# solar_power.net
KiCad netlist of a schematic drawn in Altium Designer
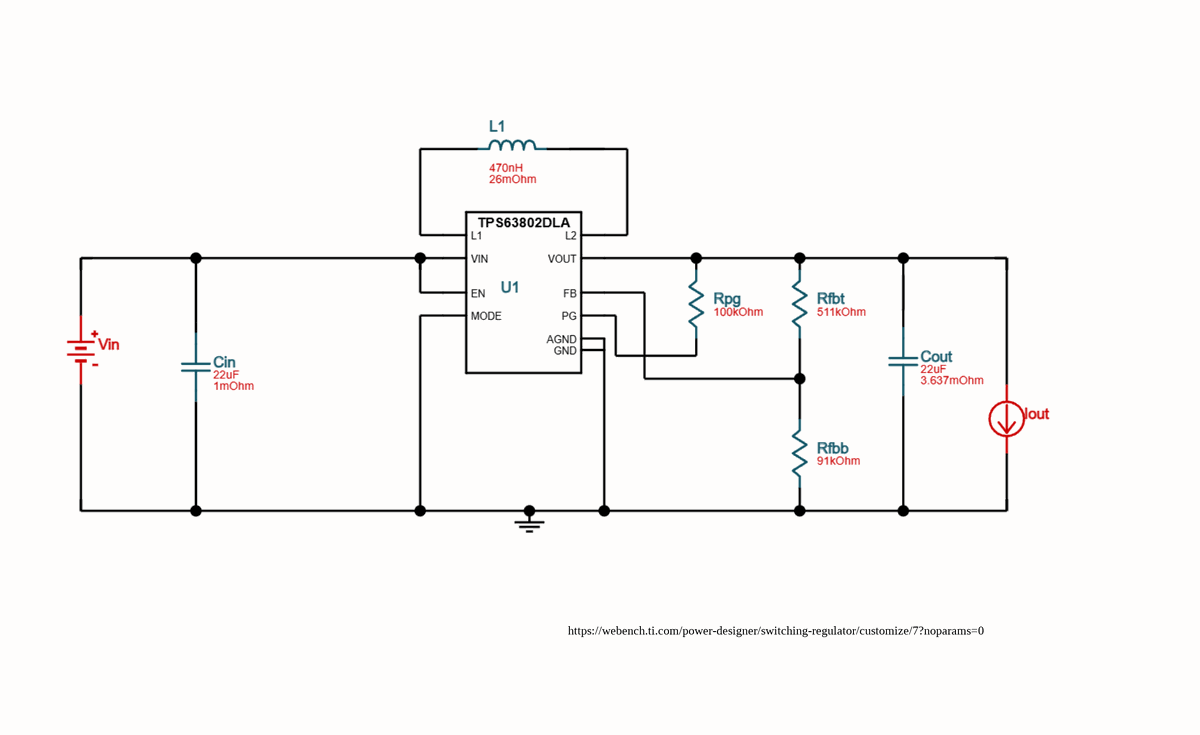
[diagram p0: solar_power.SchDoc, left]
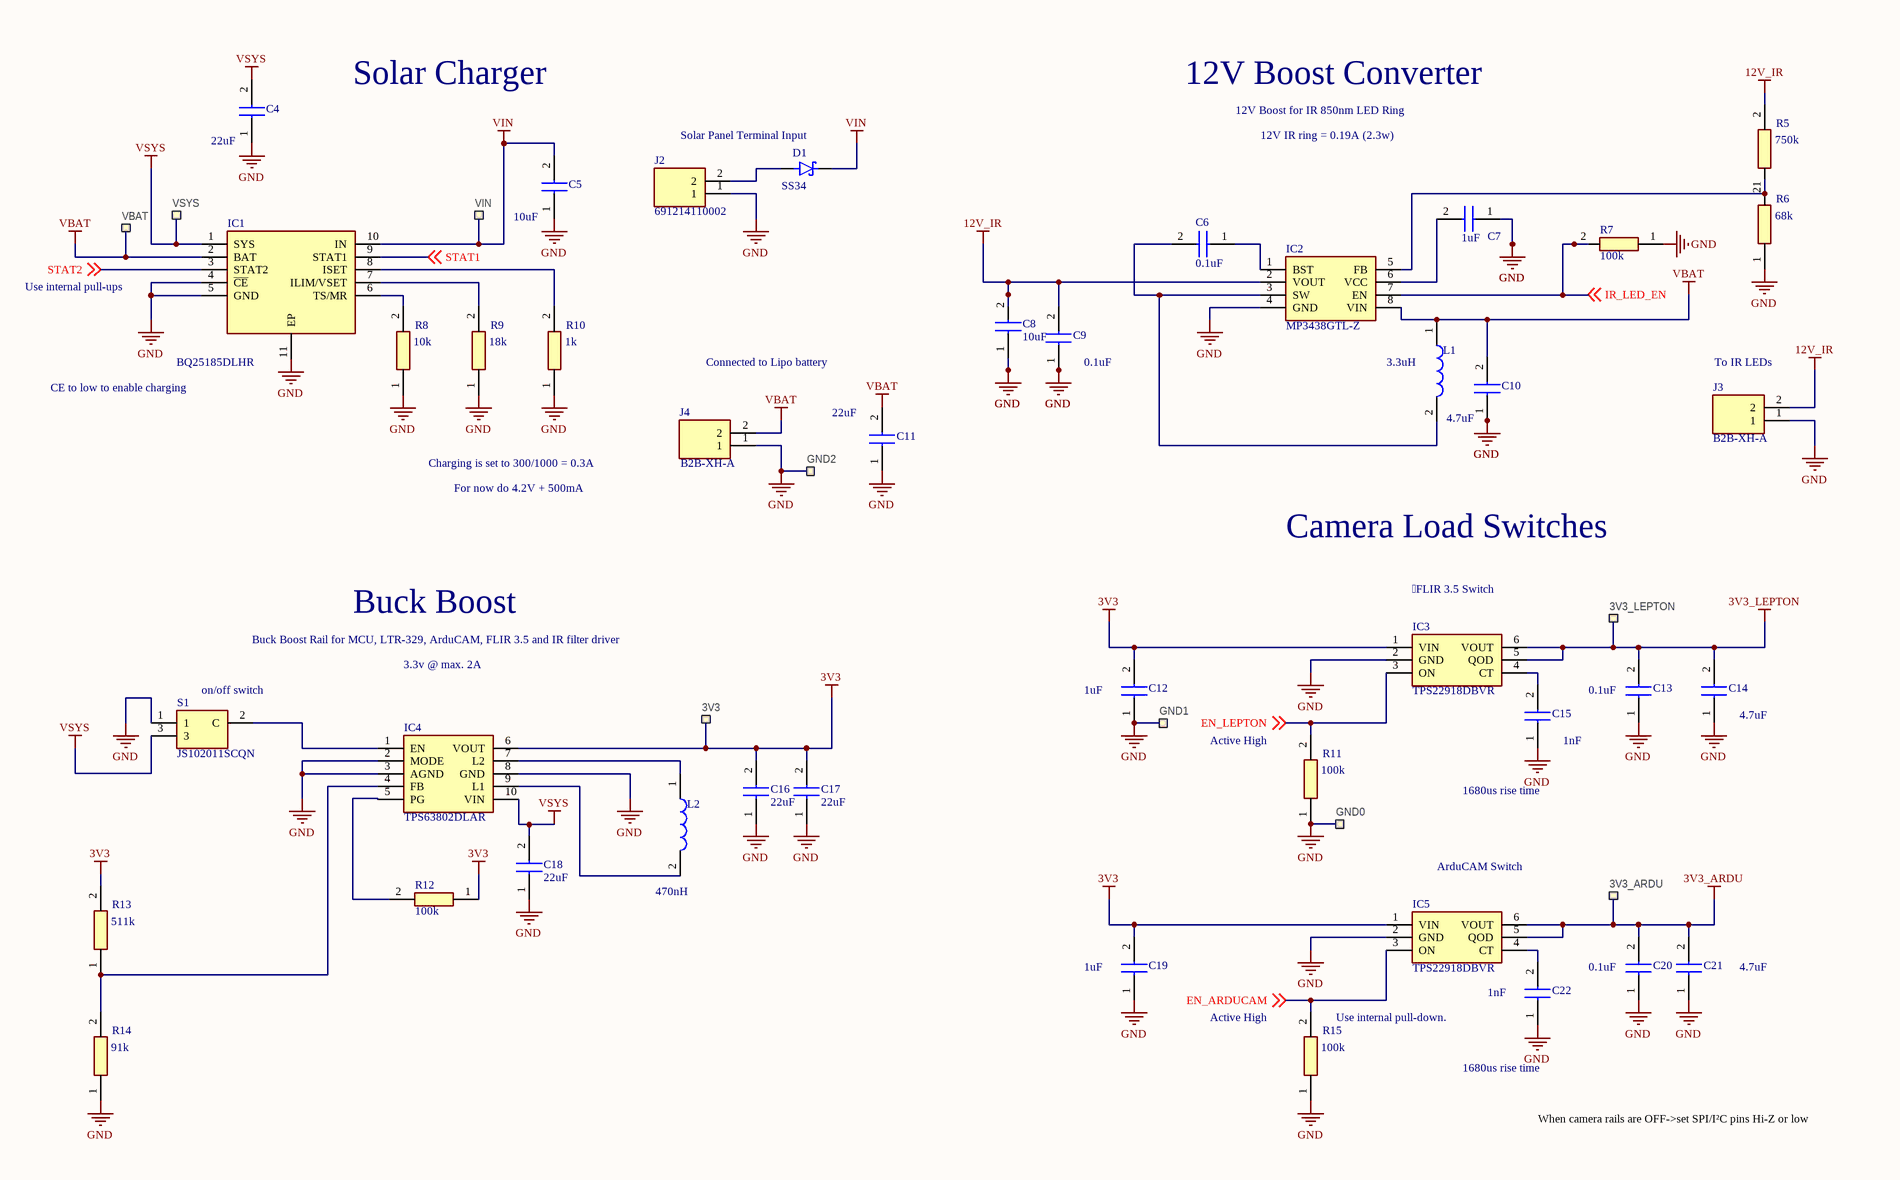
[diagram p1: solar_power.SchDoc, right]

(export (version "E")
  (design (tool "Eeschema 10.0.6"))
  (components
    (comp (ref "3V3")
      (value "Ø1.0mm,SMD")
      (footprint "TP_SMD_D1.0mm")
      (description "1.0mm circular SMD testpad")
      (fields
        (field (name "PART NUMBER") "TP_SMD_Ø1.0MM")
        (field (name "MANUFACTURER") "Nordic Semiconductor")
        (field (name "AUTHOR") "rsk")
      )
      (libsource (lib "AltiumLib") (part "TESTPAD"))
    )
    (comp (ref "3V3_ARDU")
      (value "Ø1.0mm,SMD")
      (footprint "TP_SMD_D1.0mm")
      (description "1.0mm circular SMD testpad")
      (fields
        (field (name "PART NUMBER") "TP_SMD_Ø1.0MM")
        (field (name "MANUFACTURER") "Nordic Semiconductor")
        (field (name "AUTHOR") "rsk")
      )
      (libsource (lib "AltiumLib") (part "TESTPAD"))
    )
    (comp (ref "3V3_LEPTON")
      (value "Ø1.0mm,SMD")
      (footprint "TP_SMD_D1.0mm")
      (description "1.0mm circular SMD testpad")
      (fields
        (field (name "PART NUMBER") "TP_SMD_Ø1.0MM")
        (field (name "MANUFACTURER") "Nordic Semiconductor")
        (field (name "AUTHOR") "rsk")
      )
      (libsource (lib "AltiumLib") (part "TESTPAD"))
    )
    (comp (ref "C4")
      (value "22uF")
      (footprint "SamacSys:CAPC2114X95N")
      (description "MSASL219LB5226MTNA01 0805 CAP 25V")
      (fields (field (name "MANUFACTURER_PART_NUMBER") "MSASL219LB5226MTNA01"))
      (libsource (lib "*") (part "MSASL219LB5226MTNA01"))
    )
    (comp (ref "C5")
      (value "10uF")
      (footprint "SamacSys:CAPC2114X95N")
      (description "MSASL219LB5226MTNA01 0805 CAP 25V")
      (fields (field (name "MANUFACTURER_PART_NUMBER") "MSASL219LB5226MTNA01"))
      (libsource (lib "*") (part "MSASL219LB5226MTNA01"))
    )
    (comp (ref "C6")
      (value "0.1uF")
      (footprint "SamacSys:CAPC1608X90N")
      (description "0603 CAP X5R 25V")
      (fields
        (field (name "MANUFACTURER_PART_NUMBER") "CC0603KRX7R0BB104")
        (field (name "MOUSER PART NUMBER") "603-CC603KRX7R0BB104")
      )
      (libsource (lib "*") (part "CC0603KRX7R0BB104"))
    )
    (comp (ref "C7")
      (value "1uF")
      (footprint "SamacSys:CAPC1608X90N")
      (description "0603 CAP X5R 25V")
      (fields
        (field (name "MANUFACTURER_PART_NUMBER") "CC0603KRX7R0BB104")
        (field (name "MOUSER PART NUMBER") "603-CC603KRX7R0BB104")
      )
      (libsource (lib "*") (part "CC0603KRX7R0BB104"))
    )
    (comp (ref "C8")
      (value "10uF")
      (footprint "SamacSys:CAPC2114X95N")
      (description "MSASL219LB5226MTNA01 0805 CAP 25V")
      (fields (field (name "MANUFACTURER_PART_NUMBER") "MSASL219LB5226MTNA01"))
      (libsource (lib "*") (part "MSASL219LB5226MTNA01"))
    )
    (comp (ref "C9")
      (value "0.1uF")
      (footprint "SamacSys:CAPC1608X90N")
      (description "0603 CAP X5R 25V")
      (fields
        (field (name "MANUFACTURER_PART_NUMBER") "CC0603KRX7R0BB104")
        (field (name "MOUSER PART NUMBER") "603-CC603KRX7R0BB104")
      )
      (libsource (lib "*") (part "CC0603KRX7R0BB104"))
    )
    (comp (ref "C10")
      (value "4.7uF")
      (footprint "SamacSys:CAPC2114X95N")
      (description "MSASL219LB5226MTNA01 0805 CAP 25V")
      (fields (field (name "MANUFACTURER_PART_NUMBER") "MSASL219LB5226MTNA01"))
      (libsource (lib "*") (part "MSASL219LB5226MTNA01"))
    )
    (comp (ref "C11")
      (value "22uF")
      (footprint "SamacSys:CAPC2114X95N")
      (description "MSASL219LB5226MTNA01 0805 CAP 25V")
      (fields (field (name "MANUFACTURER_PART_NUMBER") "MSASL219LB5226MTNA01"))
      (libsource (lib "*") (part "MSASL219LB5226MTNA01"))
    )
    (comp (ref "C12")
      (value "1uF")
      (footprint "SamacSys:CAPC1608X90N")
      (description "0603 CAP X5R 25V")
      (fields
        (field (name "MANUFACTURER_PART_NUMBER") "CC0603KRX7R0BB104")
        (field (name "MOUSER PART NUMBER") "603-CC603KRX7R0BB104")
      )
      (libsource (lib "*") (part "CC0603KRX7R0BB104"))
    )
    (comp (ref "C13")
      (value "0.1uF")
      (footprint "SamacSys:CAPC1608X90N")
      (description "0603 CAP X5R 25V")
      (fields
        (field (name "MANUFACTURER_PART_NUMBER") "CC0603KRX7R0BB104")
        (field (name "MOUSER PART NUMBER") "603-CC603KRX7R0BB104")
      )
      (libsource (lib "*") (part "CC0603KRX7R0BB104"))
    )
    (comp (ref "C14")
      (value "4.7uF")
      (footprint "SamacSys:CAPC1608X90N")
      (description "0603 CAP X5R 25V")
      (fields
        (field (name "MANUFACTURER_PART_NUMBER") "CC0603KRX7R0BB104")
        (field (name "MOUSER PART NUMBER") "603-CC603KRX7R0BB104")
      )
      (libsource (lib "*") (part "CC0603KRX7R0BB104"))
    )
    (comp (ref "C15")
      (value "1nF")
      (footprint "SamacSys:CAPC1608X90N")
      (description "0603 CAP X5R 50V")
      (fields
        (field (name "MANUFACTURER_PART_NUMBER") "CC0603KRX7R0BB104")
        (field (name "MOUSER PART NUMBER") "603-CC603KRX7R0BB104")
      )
      (libsource (lib "*") (part "CC0603KRX7R0BB104"))
    )
    (comp (ref "C16")
      (value "22uF")
      (footprint "SamacSys:CAPC2114X95N")
      (description "MSASL219LB5226MTNA01 0805 CAP 25V")
      (fields (field (name "MANUFACTURER_PART_NUMBER") "MSASL219LB5226MTNA01"))
      (libsource (lib "*") (part "MSASL219LB5226MTNA01"))
    )
    (comp (ref "C17")
      (value "22uF")
      (footprint "SamacSys:CAPC2114X95N")
      (description "MSASL219LB5226MTNA01 0805 CAP 25V")
      (fields (field (name "MANUFACTURER_PART_NUMBER") "MSASL219LB5226MTNA01"))
      (libsource (lib "*") (part "MSASL219LB5226MTNA01"))
    )
    (comp (ref "C18")
      (value "22uF")
      (footprint "SamacSys:CAPC2114X95N")
      (description "MSASL219LB5226MTNA01 0805 CAP 25V")
      (fields (field (name "MANUFACTURER_PART_NUMBER") "MSASL219LB5226MTNA01"))
      (libsource (lib "*") (part "MSASL219LB5226MTNA01"))
    )
    (comp (ref "C19")
      (value "1uF")
      (footprint "SamacSys:CAPC1608X90N")
      (description "0603 CAP X5R 25V")
      (fields
        (field (name "MANUFACTURER_PART_NUMBER") "CC0603KRX7R0BB104")
        (field (name "MOUSER PART NUMBER") "603-CC603KRX7R0BB104")
      )
      (libsource (lib "*") (part "CC0603KRX7R0BB104"))
    )
    (comp (ref "C20")
      (value "0.1uF")
      (footprint "SamacSys:CAPC1608X90N")
      (description "0603 CAP X5R 25V")
      (fields
        (field (name "MANUFACTURER_PART_NUMBER") "CC0603KRX7R0BB104")
        (field (name "MOUSER PART NUMBER") "603-CC603KRX7R0BB104")
      )
      (libsource (lib "*") (part "CC0603KRX7R0BB104"))
    )
    (comp (ref "C21")
      (value "4.7uF")
      (footprint "SamacSys:CAPC1608X90N")
      (description "0603 CAP X5R 25V")
      (fields
        (field (name "MANUFACTURER_PART_NUMBER") "CC0603KRX7R0BB104")
        (field (name "MOUSER PART NUMBER") "603-CC603KRX7R0BB104")
      )
      (libsource (lib "*") (part "CC0603KRX7R0BB104"))
    )
    (comp (ref "C22")
      (value "1nF")
      (footprint "SamacSys:CAPC1608X90N")
      (description "0603 CAP X5R 50V")
      (fields
        (field (name "MANUFACTURER_PART_NUMBER") "CC0603KRX7R0BB104")
        (field (name "MOUSER PART NUMBER") "603-CC603KRX7R0BB104")
      )
      (libsource (lib "*") (part "CC0603KRX7R0BB104"))
    )
    (comp (ref "D1")
      (value "SS34")
      (footprint "DIOM7959X265N")
      (description "Diode Schottky 40 V 3A Surface Mount SMC (DO-214AB)")
      (fields (field (name "MF") "onsemi"))
      (libsource (lib "SamacSys") (part "SS34"))
    )
    (comp (ref "GND0")
      (value "Ø1.0mm,SMD")
      (footprint "TP_SMD_D1.0mm")
      (description "1.0mm circular SMD testpad")
      (fields
        (field (name "PART NUMBER") "TP_SMD_Ø1.0MM")
        (field (name "MANUFACTURER") "Nordic Semiconductor")
        (field (name "AUTHOR") "rsk")
      )
      (libsource (lib "") (part "TESTPAD_1"))
    )
    (comp (ref "GND1")
      (value "Ø1.0mm,SMD")
      (footprint "TP_SMD_D1.0mm")
      (description "1.0mm circular SMD testpad")
      (fields
        (field (name "PART NUMBER") "TP_SMD_Ø1.0MM")
        (field (name "MANUFACTURER") "Nordic Semiconductor")
        (field (name "AUTHOR") "rsk")
      )
      (libsource (lib "") (part "TESTPAD_1"))
    )
    (comp (ref "GND2")
      (value "Ø1.0mm,SMD")
      (footprint "TP_SMD_D1.0mm")
      (description "1.0mm circular SMD testpad")
      (fields
        (field (name "PART NUMBER") "TP_SMD_Ø1.0MM")
        (field (name "MANUFACTURER") "Nordic Semiconductor")
        (field (name "AUTHOR") "rsk")
      )
      (libsource (lib "") (part "TESTPAD_1"))
    )
    (comp (ref "IC1")
      (value "BQ25185DLHR")
      (footprint "SamacSys:SON40P220X200X80-11N")
      (description "Integrated Circuit")
      (fields (field (name "MOUSER PART NUMBER") "595-BQ25185DLHR"))
      (libsource (lib "*") (part "BQ25185DLHR"))
    )
    (comp (ref "IC2")
      (value "MP3438GTL-Z")
      (footprint "SamacSys:SOTFL50P160X60-8N")
      (description "Integrated Circuit")
      (fields (field (name "MOUSER PART NUMBER") "946-MP3438GTL-Z"))
      (libsource (lib "*") (part "MP3438GTL-Z"))
    )
    (comp (ref "IC3")
      (value "TPS22918DBVR")
      (footprint "SamacSys:SOT95P280X145-6N")
      (description "Integrated Circuit")
      (fields (field (name "MOUSER PART NUMBER") "595-TPS22918DBVR"))
      (libsource (lib "*") (part "TPS22918DBVR"))
    )
    (comp (ref "IC4")
      (value "TPS63802DLAR")
      (footprint "SamacSys:TPS63802DLAR")
      (description "Integrated Circuit")
      (fields (field (name "MOUSER PART NUMBER") "595-TPS63802DLAR"))
      (libsource (lib "*") (part "TPS63802DLAR"))
    )
    (comp (ref "IC5")
      (value "TPS22918DBVR")
      (footprint "SamacSys:SOT95P280X145-6N")
      (description "Integrated Circuit")
      (fields (field (name "MOUSER PART NUMBER") "595-TPS22918DBVR"))
      (libsource (lib "*") (part "TPS22918DBVR"))
    )
    (comp (ref "J2")
      (value "691214110002")
      (footprint "SamacSys:691214110002")
      (description "Connector")
      (fields (field (name "MOUSER PART NUMBER") "710-691214110002"))
      (libsource (lib "*") (part "691214110002"))
    )
    (comp (ref "J3")
      (value "B2B-XH-A")
      (footprint "SamacSys:SHDR2W64P0X250_1X2_740X575X700P")
      (description "Connector")
      (libsource (lib "*") (part "B2B-XH-A"))
    )
    (comp (ref "J4")
      (value "B2B-XH-A")
      (footprint "SamacSys:SHDR2W64P0X250_1X2_740X575X700P")
      (description "Connector")
      (libsource (lib "*") (part "B2B-XH-A"))
    )
    (comp (ref "L1")
      (value "3.3uH")
      (footprint "SamacSys:MPLAL40203R3")
      (description "MPL-AL4020-3R3")
      (fields (field (name "MOUSER PART NUMBER") "946-MPL-AL4020-3R3"))
      (libsource (lib "*") (part "MPL-AL4020-3R3"))
    )
    (comp (ref "L2")
      (value "470nH")
      (footprint "SamacSys:1285ASH1R0MP2")
      (description "DFE201610E-R47M=P2")
      (fields (field (name "MOUSER PART NUMBER") "81-DFE201610E-R47MP2"))
      (libsource (lib "*") (part "DFE201610E-R47M=P2"))
    )
    (comp (ref "R5")
      (value "750k")
      (footprint "SamacSys:RESC1608X55N")
      (description "Resistor SMD 0603 1% 0.25W")
      (fields (field (name "MANUFACTURER_PART_NUMBER") "RC0603FR0710KL"))
      (libsource (lib "") (part "RC0603FR0710KL_1"))
    )
    (comp (ref "R6")
      (value "68k")
      (footprint "SamacSys:RESC1608X55N")
      (description "Resistor SMD 0603 1% 0.25W")
      (fields (field (name "MANUFACTURER_PART_NUMBER") "RC0603FR0710KL"))
      (libsource (lib "") (part "RC0603FR0710KL_1"))
    )
    (comp (ref "R7")
      (value "100k")
      (footprint "SamacSys:RESC1608X55N")
      (description "Resistor SMD 0603 1% 0.1W")
      (fields (field (name "MANUFACTURER_PART_NUMBER") "RC0603FR0710KL"))
      (libsource (lib "*") (part "RC0603FR0710KL"))
    )
    (comp (ref "R8")
      (value "10k")
      (footprint "SamacSys:RESC1608X55N")
      (description "Resistor SMD 0603 1% 1/10")
      (fields (field (name "MANUFACTURER_PART_NUMBER") "RC0603FR0710KL"))
      (libsource (lib "") (part "RC0603FR0710KL_1"))
    )
    (comp (ref "R9")
      (value "18k")
      (footprint "SamacSys:RESC1608X55N")
      (description "Resistor SMD 0603 1% 1/10")
      (fields (field (name "MANUFACTURER_PART_NUMBER") "RC0603FR0710KL"))
      (libsource (lib "") (part "RC0603FR0710KL_1"))
    )
    (comp (ref "R10")
      (value "1k")
      (footprint "SamacSys:RESC1608X55N")
      (description "Resistor SMD 0603 1% 1/10")
      (fields (field (name "MANUFACTURER_PART_NUMBER") "RC0603FR0710KL"))
      (libsource (lib "") (part "RC0603FR0710KL_1"))
    )
    (comp (ref "R11")
      (value "100k")
      (footprint "SamacSys:RESC1608X55N")
      (description "Resistor SMD 0603 1% 0.1W")
      (fields (field (name "MANUFACTURER_PART_NUMBER") "RC0603FR0710KL"))
      (libsource (lib "") (part "RC0603FR0710KL_1"))
    )
    (comp (ref "R12")
      (value "100k")
      (footprint "SamacSys:RESC1608X55N")
      (description "Resistor SMD 0603 1% 0.1W")
      (fields (field (name "MANUFACTURER_PART_NUMBER") "RC0603FR0710KL"))
      (libsource (lib "*") (part "RC0603FR0710KL"))
    )
    (comp (ref "R13")
      (value "511k")
      (footprint "SamacSys:RESC1608X55N")
      (description "Resistor SMD 0603 1% 1/10")
      (fields (field (name "MANUFACTURER_PART_NUMBER") "RC0603FR0710KL"))
      (libsource (lib "") (part "RC0603FR0710KL_1"))
    )
    (comp (ref "R14")
      (value "91k")
      (footprint "SamacSys:RESC1608X55N")
      (description "Resistor SMD 0603 1% 1/10")
      (fields (field (name "MANUFACTURER_PART_NUMBER") "RC0603FR0710KL"))
      (libsource (lib "") (part "RC0603FR0710KL_1"))
    )
    (comp (ref "R15")
      (value "100k")
      (footprint "SamacSys:RESC1608X55N")
      (description "Resistor SMD 0603 1% 0.1W")
      (fields (field (name "MANUFACTURER_PART_NUMBER") "RC0603FR0710KL"))
      (libsource (lib "") (part "RC0603FR0710KL_1"))
    )
    (comp (ref "S1")
      (value "JS102011SCQN")
      (footprint "SamacSys:JS102011SCQN")
      (description "Switch")
      (fields (field (name "MOUSER PART NUMBER") "611-JS102011SCQN"))
      (libsource (lib "*") (part "JS102011SCQN"))
    )
    (comp (ref "VBAT")
      (value "Ø1.0mm,SMD")
      (footprint "TP_SMD_D1.0mm")
      (description "1.0mm circular SMD testpad")
      (fields
        (field (name "PART NUMBER") "TP_SMD_Ø1.0MM")
        (field (name "MANUFACTURER") "Nordic Semiconductor")
        (field (name "AUTHOR") "rsk")
      )
      (libsource (lib "AltiumLib") (part "TESTPAD"))
    )
    (comp (ref "VIN")
      (value "Ø1.0mm,SMD")
      (footprint "TP_SMD_D1.0mm")
      (description "1.0mm circular SMD testpad")
      (fields
        (field (name "PART NUMBER") "TP_SMD_Ø1.0MM")
        (field (name "MANUFACTURER") "Nordic Semiconductor")
        (field (name "AUTHOR") "rsk")
      )
      (libsource (lib "AltiumLib") (part "TESTPAD"))
    )
    (comp (ref "VSYS")
      (value "Ø1.0mm,SMD")
      (footprint "TP_SMD_D1.0mm")
      (description "1.0mm circular SMD testpad")
      (fields
        (field (name "PART NUMBER") "TP_SMD_Ø1.0MM")
        (field (name "MANUFACTURER") "Nordic Semiconductor")
        (field (name "AUTHOR") "rsk")
      )
      (libsource (lib "AltiumLib") (part "TESTPAD"))
    )
  )
  (nets
    (net (code "1") (name "3V3") (class "Default")
      (node (ref "3V3") (pin "1") (pinfunction "1_1") (pintype "passive"))
      (node (ref "C12") (pin "2") (pinfunction "2_2") (pintype "passive"))
      (node (ref "C16") (pin "2") (pinfunction "2_2") (pintype "passive"))
      (node (ref "C17") (pin "2") (pinfunction "2_2") (pintype "passive"))
      (node (ref "C19") (pin "2") (pinfunction "2_2") (pintype "passive"))
      (node (ref "IC3") (pin "1") (pinfunction "VIN_1") (pintype "passive"))
      (node (ref "IC4") (pin "6") (pinfunction "VOUT_6") (pintype "passive"))
      (node (ref "IC5") (pin "1") (pinfunction "VIN_1") (pintype "passive"))
      (node (ref "R12") (pin "1") (pinfunction "1_1") (pintype "passive"))
      (node (ref "R13") (pin "2") (pinfunction "2_2") (pintype "passive"))
    )
    (net (code "2") (name "3V3_ARDU") (class "Default")
      (node (ref "3V3_ARDU") (pin "1") (pinfunction "1_1") (pintype "passive"))
      (node (ref "C20") (pin "2") (pinfunction "2_2") (pintype "passive"))
      (node (ref "C21") (pin "2") (pinfunction "2_2") (pintype "passive"))
      (node (ref "IC5") (pin "5") (pinfunction "QOD_5") (pintype "passive"))
      (node (ref "IC5") (pin "6") (pinfunction "VOUT_6") (pintype "passive"))
    )
    (net (code "3") (name "3V3_LEPTON") (class "Default")
      (node (ref "3V3_LEPTON") (pin "1") (pinfunction "1_1") (pintype "passive"))
      (node (ref "C13") (pin "2") (pinfunction "2_2") (pintype "passive"))
      (node (ref "C14") (pin "2") (pinfunction "2_2") (pintype "passive"))
      (node (ref "IC3") (pin "5") (pinfunction "QOD_5") (pintype "passive"))
      (node (ref "IC3") (pin "6") (pinfunction "VOUT_6") (pintype "passive"))
    )
    (net (code "4") (name "12V_IR") (class "Default")
      (node (ref "C8") (pin "2") (pinfunction "2_2") (pintype "passive"))
      (node (ref "C9") (pin "2") (pinfunction "2_2") (pintype "passive"))
      (node (ref "IC2") (pin "2") (pinfunction "VOUT_2") (pintype "passive"))
      (node (ref "J3") (pin "2") (pinfunction "2_2") (pintype "passive"))
      (node (ref "R5") (pin "2") (pinfunction "2_2") (pintype "passive"))
    )
    (net (code "5") (name "EN_ARDUCAM") (class "Default")
      (node (ref "IC5") (pin "3") (pinfunction "ON_3") (pintype "passive"))
      (node (ref "R15") (pin "2") (pinfunction "2_2") (pintype "passive"))
    )
    (net (code "6") (name "EN_LEPTON") (class "Default")
      (node (ref "IC3") (pin "3") (pinfunction "ON_3") (pintype "passive"))
      (node (ref "R11") (pin "2") (pinfunction "2_2") (pintype "passive"))
    )
    (net (code "7") (name "GND") (class "Default")
      (node (ref "C10") (pin "1") (pinfunction "1_1") (pintype "passive"))
      (node (ref "C11") (pin "1") (pinfunction "1_1") (pintype "passive"))
      (node (ref "C12") (pin "1") (pinfunction "1_1") (pintype "passive"))
      (node (ref "C13") (pin "1") (pinfunction "1_1") (pintype "passive"))
      (node (ref "C14") (pin "1") (pinfunction "1_1") (pintype "passive"))
      (node (ref "C15") (pin "1") (pinfunction "1_1") (pintype "passive"))
      (node (ref "C16") (pin "1") (pinfunction "1_1") (pintype "passive"))
      (node (ref "C17") (pin "1") (pinfunction "1_1") (pintype "passive"))
      (node (ref "C18") (pin "1") (pinfunction "1_1") (pintype "passive"))
      (node (ref "C19") (pin "1") (pinfunction "1_1") (pintype "passive"))
      (node (ref "C20") (pin "1") (pinfunction "1_1") (pintype "passive"))
      (node (ref "C21") (pin "1") (pinfunction "1_1") (pintype "passive"))
      (node (ref "C22") (pin "1") (pinfunction "1_1") (pintype "passive"))
      (node (ref "C4") (pin "1") (pinfunction "1_1") (pintype "passive"))
      (node (ref "C5") (pin "1") (pinfunction "1_1") (pintype "passive"))
      (node (ref "C7") (pin "1") (pinfunction "1_1") (pintype "passive"))
      (node (ref "C8") (pin "1") (pinfunction "1_1") (pintype "passive"))
      (node (ref "C9") (pin "1") (pinfunction "1_1") (pintype "passive"))
      (node (ref "GND0") (pin "1") (pinfunction "1_1") (pintype "passive"))
      (node (ref "GND1") (pin "1") (pinfunction "1_1") (pintype "passive"))
      (node (ref "GND2") (pin "1") (pinfunction "1_1") (pintype "passive"))
      (node (ref "IC1") (pin "11") (pinfunction "EP_11") (pintype "passive"))
      (node (ref "IC1") (pin "4") (pinfunction "~{CE}_4") (pintype "passive"))
      (node (ref "IC1") (pin "5") (pinfunction "GND_5") (pintype "passive"))
      (node (ref "IC2") (pin "4") (pinfunction "GND_4") (pintype "passive"))
      (node (ref "IC3") (pin "2") (pinfunction "GND_2") (pintype "passive"))
      (node (ref "IC4") (pin "2") (pinfunction "MODE_2") (pintype "passive"))
      (node (ref "IC4") (pin "3") (pinfunction "AGND_3") (pintype "passive"))
      (node (ref "IC4") (pin "8") (pinfunction "GND_8") (pintype "passive"))
      (node (ref "IC5") (pin "2") (pinfunction "GND_2") (pintype "passive"))
      (node (ref "J2") (pin "1") (pinfunction "1_1") (pintype "passive"))
      (node (ref "J3") (pin "1") (pinfunction "1_1") (pintype "passive"))
      (node (ref "J4") (pin "1") (pinfunction "1_1") (pintype "passive"))
      (node (ref "R10") (pin "1") (pinfunction "1_1") (pintype "passive"))
      (node (ref "R11") (pin "1") (pinfunction "1_1") (pintype "passive"))
      (node (ref "R14") (pin "1") (pinfunction "1_1") (pintype "passive"))
      (node (ref "R15") (pin "1") (pinfunction "1_1") (pintype "passive"))
      (node (ref "R6") (pin "1") (pinfunction "1_1") (pintype "passive"))
      (node (ref "R7") (pin "1") (pinfunction "1_1") (pintype "passive"))
      (node (ref "R8") (pin "1") (pinfunction "1_1") (pintype "passive"))
      (node (ref "R9") (pin "1") (pinfunction "1_1") (pintype "passive"))
      (node (ref "S1") (pin "1") (pinfunction "1_1") (pintype "passive"))
    )
    (net (code "8") (name "IR_LED_EN") (class "Default")
      (node (ref "IC2") (pin "7") (pinfunction "EN_7") (pintype "passive"))
      (node (ref "R7") (pin "2") (pinfunction "2_2") (pintype "passive"))
    )
    (net (code "9") (name "Net-(D1-PadA)") (class "Default")
      (node (ref "D1") (pin "A") (pinfunction "A_A") (pintype "passive"))
      (node (ref "J2") (pin "2") (pinfunction "2_2") (pintype "passive"))
    )
    (net (code "10") (name "Net-(IC1-ILIM{slash}VSET)") (class "Default")
      (node (ref "IC1") (pin "7") (pinfunction "ILIM/VSET_7") (pintype "passive"))
      (node (ref "R9") (pin "2") (pinfunction "2_2") (pintype "passive"))
    )
    (net (code "11") (name "Net-(IC1-ISET)") (class "Default")
      (node (ref "IC1") (pin "8") (pinfunction "ISET_8") (pintype "passive"))
      (node (ref "R10") (pin "2") (pinfunction "2_2") (pintype "passive"))
    )
    (net (code "12") (name "Net-(IC1-TS{slash}MR)") (class "Default")
      (node (ref "IC1") (pin "6") (pinfunction "TS/MR_6") (pintype "passive"))
      (node (ref "R8") (pin "2") (pinfunction "2_2") (pintype "passive"))
    )
    (net (code "13") (name "Net-(IC2-BST)") (class "Default")
      (node (ref "C6") (pin "1") (pinfunction "1_1") (pintype "passive"))
      (node (ref "IC2") (pin "1") (pinfunction "BST_1") (pintype "passive"))
    )
    (net (code "14") (name "Net-(IC2-FB)") (class "Default")
      (node (ref "IC2") (pin "5") (pinfunction "FB_5") (pintype "passive"))
      (node (ref "R5") (pin "1") (pinfunction "1_1") (pintype "passive"))
      (node (ref "R6") (pin "2") (pinfunction "2_2") (pintype "passive"))
    )
    (net (code "15") (name "Net-(IC2-SW)") (class "Default")
      (node (ref "C6") (pin "2") (pinfunction "2_2") (pintype "passive"))
      (node (ref "IC2") (pin "3") (pinfunction "SW_3") (pintype "passive"))
      (node (ref "L1") (pin "2") (pinfunction "2_2") (pintype "passive"))
    )
    (net (code "16") (name "Net-(IC2-VCC)") (class "Default")
      (node (ref "C7") (pin "2") (pinfunction "2_2") (pintype "passive"))
      (node (ref "IC2") (pin "6") (pinfunction "VCC_6") (pintype "passive"))
    )
    (net (code "17") (name "Net-(IC3-CT)") (class "Default")
      (node (ref "C15") (pin "2") (pinfunction "2_2") (pintype "passive"))
      (node (ref "IC3") (pin "4") (pinfunction "CT_4") (pintype "passive"))
    )
    (net (code "18") (name "Net-(IC4-EN)") (class "Default")
      (node (ref "IC4") (pin "1") (pinfunction "EN_1") (pintype "passive"))
      (node (ref "S1") (pin "2") (pinfunction "C_2") (pintype "passive"))
    )
    (net (code "19") (name "Net-(IC4-FB)") (class "Default")
      (node (ref "IC4") (pin "4") (pinfunction "FB_4") (pintype "passive"))
      (node (ref "R13") (pin "1") (pinfunction "1_1") (pintype "passive"))
      (node (ref "R14") (pin "2") (pinfunction "2_2") (pintype "passive"))
    )
    (net (code "20") (name "Net-(IC4-L1)") (class "Default")
      (node (ref "IC4") (pin "9") (pinfunction "L1_9") (pintype "passive"))
      (node (ref "L2") (pin "2") (pinfunction "2_2") (pintype "passive"))
    )
    (net (code "21") (name "Net-(IC4-L2)") (class "Default")
      (node (ref "IC4") (pin "7") (pinfunction "L2_7") (pintype "passive"))
      (node (ref "L2") (pin "1") (pinfunction "1_1") (pintype "passive"))
    )
    (net (code "22") (name "Net-(IC4-PG)") (class "Default")
      (node (ref "IC4") (pin "5") (pinfunction "PG_5") (pintype "passive"))
      (node (ref "R12") (pin "2") (pinfunction "2_2") (pintype "passive"))
    )
    (net (code "23") (name "Net-(IC5-CT)") (class "Default")
      (node (ref "C22") (pin "2") (pinfunction "2_2") (pintype "passive"))
      (node (ref "IC5") (pin "4") (pinfunction "CT_4") (pintype "passive"))
    )
    (net (code "24") (name "STAT1") (class "Default")
      (node (ref "IC1") (pin "9") (pinfunction "STAT1_9") (pintype "passive"))
    )
    (net (code "25") (name "STAT2") (class "Default")
      (node (ref "IC1") (pin "3") (pinfunction "STAT2_3") (pintype "passive"))
    )
    (net (code "26") (name "VBAT") (class "Default")
      (node (ref "C10") (pin "2") (pinfunction "2_2") (pintype "passive"))
      (node (ref "C11") (pin "2") (pinfunction "2_2") (pintype "passive"))
      (node (ref "IC1") (pin "2") (pinfunction "BAT_2") (pintype "passive"))
      (node (ref "IC2") (pin "8") (pinfunction "VIN_8") (pintype "passive"))
      (node (ref "J4") (pin "2") (pinfunction "2_2") (pintype "passive"))
      (node (ref "L1") (pin "1") (pinfunction "1_1") (pintype "passive"))
      (node (ref "VBAT") (pin "1") (pinfunction "1_1") (pintype "passive"))
    )
    (net (code "27") (name "VIN") (class "Default")
      (node (ref "C5") (pin "2") (pinfunction "2_2") (pintype "passive"))
      (node (ref "D1") (pin "C") (pinfunction "K_C") (pintype "passive"))
      (node (ref "IC1") (pin "10") (pinfunction "IN_10") (pintype "passive"))
      (node (ref "VIN") (pin "1") (pinfunction "1_1") (pintype "passive"))
    )
    (net (code "28") (name "VSYS") (class "Default")
      (node (ref "C18") (pin "2") (pinfunction "2_2") (pintype "passive"))
      (node (ref "C4") (pin "2") (pinfunction "2_2") (pintype "passive"))
      (node (ref "IC1") (pin "1") (pinfunction "SYS_1") (pintype "passive"))
      (node (ref "IC4") (pin "10") (pinfunction "VIN_10") (pintype "passive"))
      (node (ref "S1") (pin "3") (pinfunction "3_3") (pintype "passive"))
      (node (ref "VSYS") (pin "1") (pinfunction "1_1") (pintype "passive"))
    )
  )
)
